# Circuit.net
KiCad netlist of a schematic drawn in EAGLE
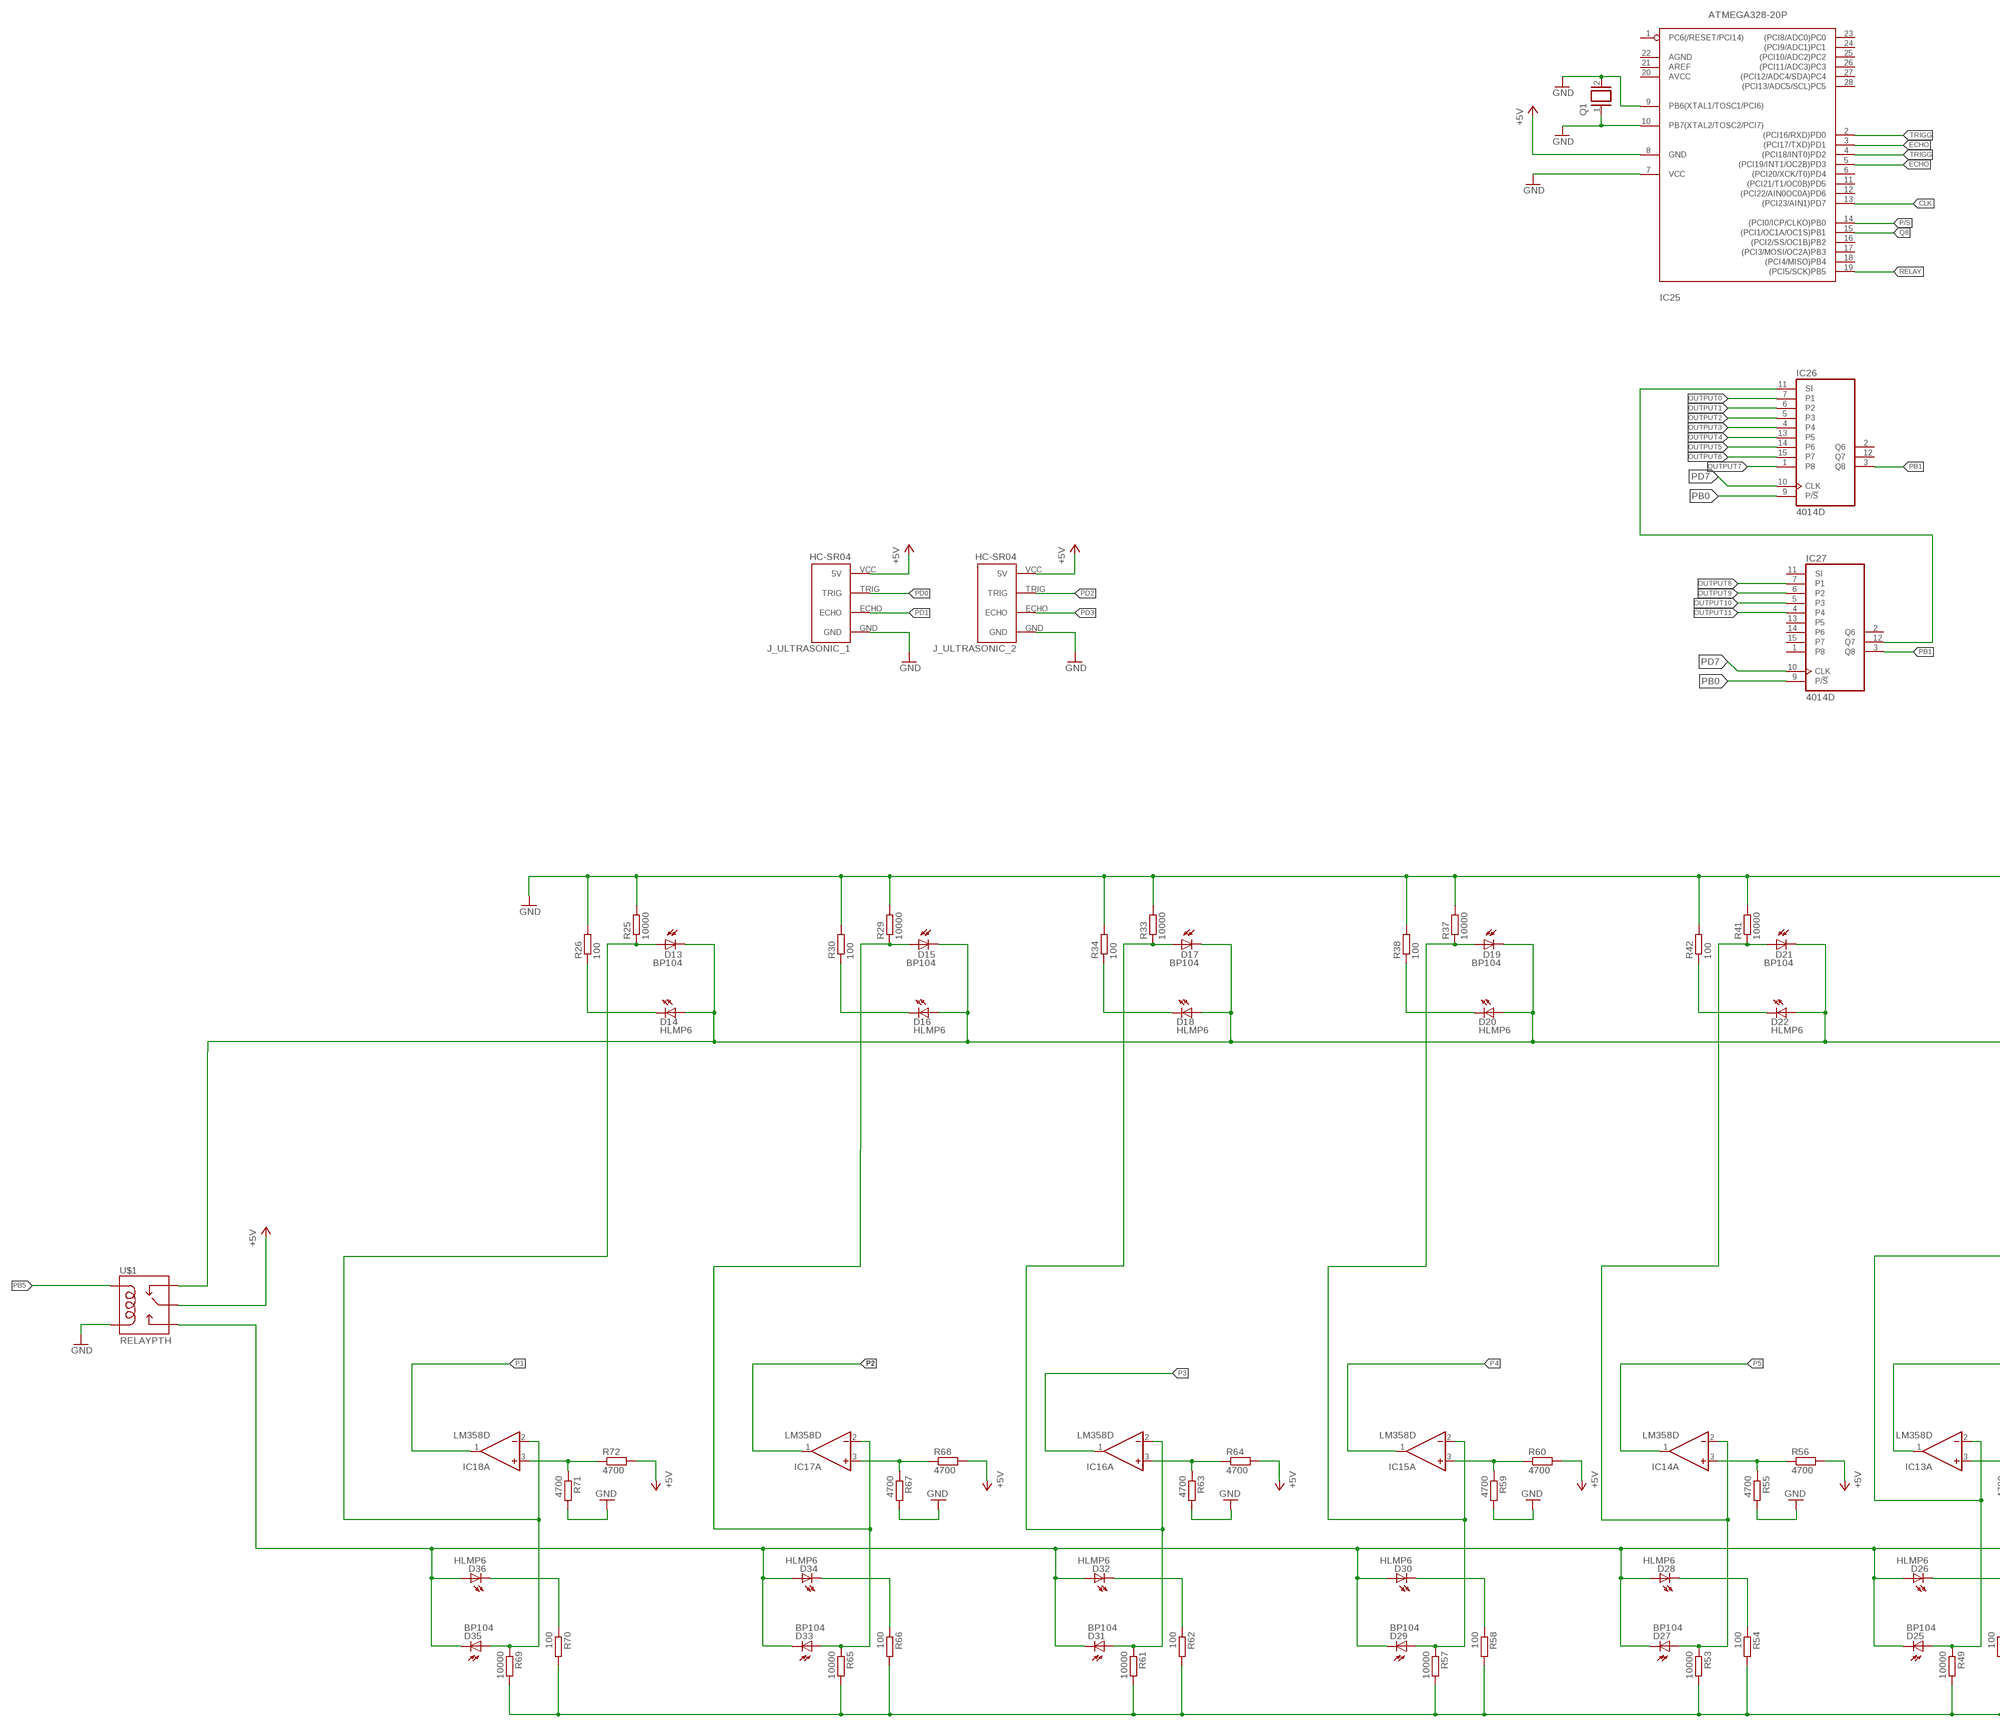
[diagram p0: schematic, sheet 1, part 1 of 2]
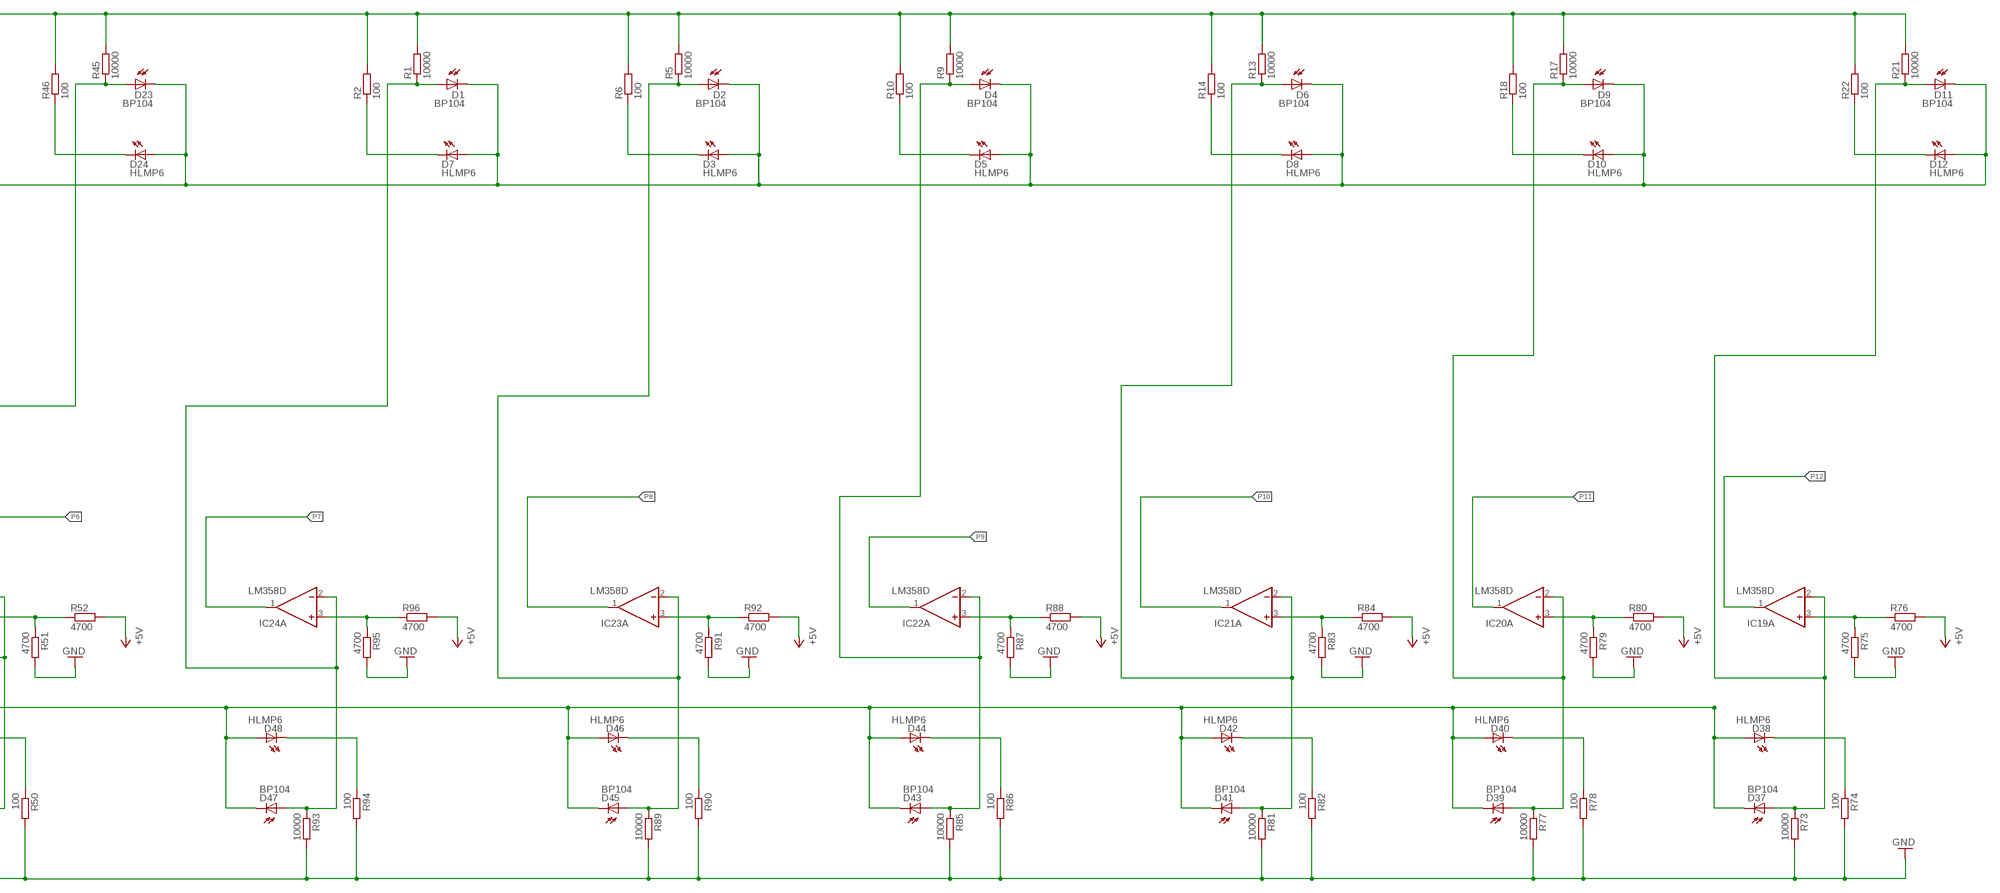
[diagram p1: schematic, sheet 1, part 2 of 2]

(export (version "E")
  (design (tool "Eeschema 10.0.6"))
  (components
    (comp (ref "D1")
      (value "BP104")
      (footprint "eagle-import:BP104")
      (fields (field (name "MF") "VISHAY/TELEFUNKEN"))
      (libsource (lib "eagle-import") (part "BP104"))
    )
    (comp (ref "D2")
      (value "BP104")
      (footprint "eagle-import:BP104")
      (fields (field (name "MF") "VISHAY/TELEFUNKEN"))
      (libsource (lib "eagle-import") (part "BP104"))
    )
    (comp (ref "D3")
      (value "HLMP6")
      (footprint "eagle-import:HLMP6")
      (fields (field (name "MF") "AGILENT TECHNOLOGIES") (field (name "MPN") "HLMP-6500"))
      (libsource (lib "eagle-import") (part "HLMP6"))
    )
    (comp (ref "D4")
      (value "BP104")
      (footprint "eagle-import:BP104")
      (fields (field (name "MF") "VISHAY/TELEFUNKEN"))
      (libsource (lib "eagle-import") (part "BP104"))
    )
    (comp (ref "D5")
      (value "HLMP6")
      (footprint "eagle-import:HLMP6")
      (fields (field (name "MF") "AGILENT TECHNOLOGIES") (field (name "MPN") "HLMP-6500"))
      (libsource (lib "eagle-import") (part "HLMP6"))
    )
    (comp (ref "D6")
      (value "BP104")
      (footprint "eagle-import:BP104")
      (fields (field (name "MF") "VISHAY/TELEFUNKEN"))
      (libsource (lib "eagle-import") (part "BP104"))
    )
    (comp (ref "D7")
      (value "HLMP6")
      (footprint "eagle-import:HLMP6")
      (fields (field (name "MF") "AGILENT TECHNOLOGIES") (field (name "MPN") "HLMP-6500"))
      (libsource (lib "eagle-import") (part "HLMP6"))
    )
    (comp (ref "D8")
      (value "HLMP6")
      (footprint "eagle-import:HLMP6")
      (fields (field (name "MF") "AGILENT TECHNOLOGIES") (field (name "MPN") "HLMP-6500"))
      (libsource (lib "eagle-import") (part "HLMP6"))
    )
    (comp (ref "D9")
      (value "BP104")
      (footprint "eagle-import:BP104")
      (fields (field (name "MF") "VISHAY/TELEFUNKEN"))
      (libsource (lib "eagle-import") (part "BP104"))
    )
    (comp (ref "D10")
      (value "HLMP6")
      (footprint "eagle-import:HLMP6")
      (fields (field (name "MF") "AGILENT TECHNOLOGIES") (field (name "MPN") "HLMP-6500"))
      (libsource (lib "eagle-import") (part "HLMP6"))
    )
    (comp (ref "D11")
      (value "BP104")
      (footprint "eagle-import:BP104")
      (fields (field (name "MF") "VISHAY/TELEFUNKEN"))
      (libsource (lib "eagle-import") (part "BP104"))
    )
    (comp (ref "D12")
      (value "HLMP6")
      (footprint "eagle-import:HLMP6")
      (fields (field (name "MF") "AGILENT TECHNOLOGIES") (field (name "MPN") "HLMP-6500"))
      (libsource (lib "eagle-import") (part "HLMP6"))
    )
    (comp (ref "D13")
      (value "BP104")
      (footprint "eagle-import:BP104")
      (fields (field (name "MF") "VISHAY/TELEFUNKEN"))
      (libsource (lib "eagle-import") (part "BP104"))
    )
    (comp (ref "D14")
      (value "HLMP6")
      (footprint "eagle-import:HLMP6")
      (fields (field (name "MF") "AGILENT TECHNOLOGIES") (field (name "MPN") "HLMP-6500"))
      (libsource (lib "eagle-import") (part "HLMP6"))
    )
    (comp (ref "D15")
      (value "BP104")
      (footprint "eagle-import:BP104")
      (fields (field (name "MF") "VISHAY/TELEFUNKEN"))
      (libsource (lib "eagle-import") (part "BP104"))
    )
    (comp (ref "D16")
      (value "HLMP6")
      (footprint "eagle-import:HLMP6")
      (fields (field (name "MF") "AGILENT TECHNOLOGIES") (field (name "MPN") "HLMP-6500"))
      (libsource (lib "eagle-import") (part "HLMP6"))
    )
    (comp (ref "D17")
      (value "BP104")
      (footprint "eagle-import:BP104")
      (fields (field (name "MF") "VISHAY/TELEFUNKEN"))
      (libsource (lib "eagle-import") (part "BP104"))
    )
    (comp (ref "D18")
      (value "HLMP6")
      (footprint "eagle-import:HLMP6")
      (fields (field (name "MF") "AGILENT TECHNOLOGIES") (field (name "MPN") "HLMP-6500"))
      (libsource (lib "eagle-import") (part "HLMP6"))
    )
    (comp (ref "D19")
      (value "BP104")
      (footprint "eagle-import:BP104")
      (fields (field (name "MF") "VISHAY/TELEFUNKEN"))
      (libsource (lib "eagle-import") (part "BP104"))
    )
    (comp (ref "D20")
      (value "HLMP6")
      (footprint "eagle-import:HLMP6")
      (fields (field (name "MF") "AGILENT TECHNOLOGIES") (field (name "MPN") "HLMP-6500"))
      (libsource (lib "eagle-import") (part "HLMP6"))
    )
    (comp (ref "D21")
      (value "BP104")
      (footprint "eagle-import:BP104")
      (fields (field (name "MF") "VISHAY/TELEFUNKEN"))
      (libsource (lib "eagle-import") (part "BP104"))
    )
    (comp (ref "D22")
      (value "HLMP6")
      (footprint "eagle-import:HLMP6")
      (fields (field (name "MF") "AGILENT TECHNOLOGIES") (field (name "MPN") "HLMP-6500"))
      (libsource (lib "eagle-import") (part "HLMP6"))
    )
    (comp (ref "D23")
      (value "BP104")
      (footprint "eagle-import:BP104")
      (fields (field (name "MF") "VISHAY/TELEFUNKEN"))
      (libsource (lib "eagle-import") (part "BP104"))
    )
    (comp (ref "D24")
      (value "HLMP6")
      (footprint "eagle-import:HLMP6")
      (fields (field (name "MF") "AGILENT TECHNOLOGIES") (field (name "MPN") "HLMP-6500"))
      (libsource (lib "eagle-import") (part "HLMP6"))
    )
    (comp (ref "D25")
      (value "BP104")
      (footprint "eagle-import:BP104")
      (fields (field (name "MF") "VISHAY/TELEFUNKEN"))
      (libsource (lib "eagle-import") (part "BP104"))
    )
    (comp (ref "D26")
      (value "HLMP6")
      (footprint "eagle-import:HLMP6")
      (fields (field (name "MF") "AGILENT TECHNOLOGIES") (field (name "MPN") "HLMP-6500"))
      (libsource (lib "eagle-import") (part "HLMP6"))
    )
    (comp (ref "D27")
      (value "BP104")
      (footprint "eagle-import:BP104")
      (fields (field (name "MF") "VISHAY/TELEFUNKEN"))
      (libsource (lib "eagle-import") (part "BP104"))
    )
    (comp (ref "D28")
      (value "HLMP6")
      (footprint "eagle-import:HLMP6")
      (fields (field (name "MF") "AGILENT TECHNOLOGIES") (field (name "MPN") "HLMP-6500"))
      (libsource (lib "eagle-import") (part "HLMP6"))
    )
    (comp (ref "D29")
      (value "BP104")
      (footprint "eagle-import:BP104")
      (fields (field (name "MF") "VISHAY/TELEFUNKEN"))
      (libsource (lib "eagle-import") (part "BP104"))
    )
    (comp (ref "D30")
      (value "HLMP6")
      (footprint "eagle-import:HLMP6")
      (fields (field (name "MF") "AGILENT TECHNOLOGIES") (field (name "MPN") "HLMP-6500"))
      (libsource (lib "eagle-import") (part "HLMP6"))
    )
    (comp (ref "D31")
      (value "BP104")
      (footprint "eagle-import:BP104")
      (fields (field (name "MF") "VISHAY/TELEFUNKEN"))
      (libsource (lib "eagle-import") (part "BP104"))
    )
    (comp (ref "D32")
      (value "HLMP6")
      (footprint "eagle-import:HLMP6")
      (fields (field (name "MF") "AGILENT TECHNOLOGIES") (field (name "MPN") "HLMP-6500"))
      (libsource (lib "eagle-import") (part "HLMP6"))
    )
    (comp (ref "D33")
      (value "BP104")
      (footprint "eagle-import:BP104")
      (fields (field (name "MF") "VISHAY/TELEFUNKEN"))
      (libsource (lib "eagle-import") (part "BP104"))
    )
    (comp (ref "D34")
      (value "HLMP6")
      (footprint "eagle-import:HLMP6")
      (fields (field (name "MF") "AGILENT TECHNOLOGIES") (field (name "MPN") "HLMP-6500"))
      (libsource (lib "eagle-import") (part "HLMP6"))
    )
    (comp (ref "D35")
      (value "BP104")
      (footprint "eagle-import:BP104")
      (fields (field (name "MF") "VISHAY/TELEFUNKEN"))
      (libsource (lib "eagle-import") (part "BP104"))
    )
    (comp (ref "D36")
      (value "HLMP6")
      (footprint "eagle-import:HLMP6")
      (fields (field (name "MF") "AGILENT TECHNOLOGIES") (field (name "MPN") "HLMP-6500"))
      (libsource (lib "eagle-import") (part "HLMP6"))
    )
    (comp (ref "D37")
      (value "BP104")
      (footprint "eagle-import:BP104")
      (fields (field (name "MF") "VISHAY/TELEFUNKEN"))
      (libsource (lib "eagle-import") (part "BP104"))
    )
    (comp (ref "D38")
      (value "HLMP6")
      (footprint "eagle-import:HLMP6")
      (fields (field (name "MF") "AGILENT TECHNOLOGIES") (field (name "MPN") "HLMP-6500"))
      (libsource (lib "eagle-import") (part "HLMP6"))
    )
    (comp (ref "D39")
      (value "BP104")
      (footprint "eagle-import:BP104")
      (fields (field (name "MF") "VISHAY/TELEFUNKEN"))
      (libsource (lib "eagle-import") (part "BP104"))
    )
    (comp (ref "D40")
      (value "HLMP6")
      (footprint "eagle-import:HLMP6")
      (fields (field (name "MF") "AGILENT TECHNOLOGIES") (field (name "MPN") "HLMP-6500"))
      (libsource (lib "eagle-import") (part "HLMP6"))
    )
    (comp (ref "D41")
      (value "BP104")
      (footprint "eagle-import:BP104")
      (fields (field (name "MF") "VISHAY/TELEFUNKEN"))
      (libsource (lib "eagle-import") (part "BP104"))
    )
    (comp (ref "D42")
      (value "HLMP6")
      (footprint "eagle-import:HLMP6")
      (fields (field (name "MF") "AGILENT TECHNOLOGIES") (field (name "MPN") "HLMP-6500"))
      (libsource (lib "eagle-import") (part "HLMP6"))
    )
    (comp (ref "D43")
      (value "BP104")
      (footprint "eagle-import:BP104")
      (fields (field (name "MF") "VISHAY/TELEFUNKEN"))
      (libsource (lib "eagle-import") (part "BP104"))
    )
    (comp (ref "D44")
      (value "HLMP6")
      (footprint "eagle-import:HLMP6")
      (fields (field (name "MF") "AGILENT TECHNOLOGIES") (field (name "MPN") "HLMP-6500"))
      (libsource (lib "eagle-import") (part "HLMP6"))
    )
    (comp (ref "D45")
      (value "BP104")
      (footprint "eagle-import:BP104")
      (fields (field (name "MF") "VISHAY/TELEFUNKEN"))
      (libsource (lib "eagle-import") (part "BP104"))
    )
    (comp (ref "D46")
      (value "HLMP6")
      (footprint "eagle-import:HLMP6")
      (fields (field (name "MF") "AGILENT TECHNOLOGIES") (field (name "MPN") "HLMP-6500"))
      (libsource (lib "eagle-import") (part "HLMP6"))
    )
    (comp (ref "D47")
      (value "BP104")
      (footprint "eagle-import:BP104")
      (fields (field (name "MF") "VISHAY/TELEFUNKEN"))
      (libsource (lib "eagle-import") (part "BP104"))
    )
    (comp (ref "D48")
      (value "HLMP6")
      (footprint "eagle-import:HLMP6")
      (fields (field (name "MF") "AGILENT TECHNOLOGIES") (field (name "MPN") "HLMP-6500"))
      (libsource (lib "eagle-import") (part "HLMP6"))
    )
    (comp (ref "IC13")
      (value "LM358D")
      (footprint "eagle-import:SO08")
      (libsource (lib "eagle-import") (part "LM358D"))
    )
    (comp (ref "IC14")
      (value "LM358D")
      (footprint "eagle-import:SO08")
      (libsource (lib "eagle-import") (part "LM358D"))
    )
    (comp (ref "IC15")
      (value "LM358D")
      (footprint "eagle-import:SO08")
      (libsource (lib "eagle-import") (part "LM358D"))
    )
    (comp (ref "IC16")
      (value "LM358D")
      (footprint "eagle-import:SO08")
      (libsource (lib "eagle-import") (part "LM358D"))
    )
    (comp (ref "IC17")
      (value "LM358D")
      (footprint "eagle-import:SO08")
      (libsource (lib "eagle-import") (part "LM358D"))
    )
    (comp (ref "IC18")
      (value "LM358D")
      (footprint "eagle-import:SO08")
      (libsource (lib "eagle-import") (part "LM358D"))
    )
    (comp (ref "IC19")
      (value "LM358D")
      (footprint "eagle-import:SO08")
      (libsource (lib "eagle-import") (part "LM358D"))
    )
    (comp (ref "IC20")
      (value "LM358D")
      (footprint "eagle-import:SO08")
      (libsource (lib "eagle-import") (part "LM358D"))
    )
    (comp (ref "IC21")
      (value "LM358D")
      (footprint "eagle-import:SO08")
      (libsource (lib "eagle-import") (part "LM358D"))
    )
    (comp (ref "IC22")
      (value "LM358D")
      (footprint "eagle-import:SO08")
      (libsource (lib "eagle-import") (part "LM358D"))
    )
    (comp (ref "IC23")
      (value "LM358D")
      (footprint "eagle-import:SO08")
      (libsource (lib "eagle-import") (part "LM358D"))
    )
    (comp (ref "IC24")
      (value "LM358D")
      (footprint "eagle-import:SO08")
      (libsource (lib "eagle-import") (part "LM358D"))
    )
    (comp (ref "IC25")
      (value "ATMEGA328-20P")
      (footprint "eagle-import:DIL28-3")
      (libsource (lib "eagle-import") (part "ATMEGA328P-20"))
    )
    (comp (ref "IC26")
      (value "4014D")
      (footprint "eagle-import:SO16")
      (libsource (lib "eagle-import") (part "4014D"))
    )
    (comp (ref "IC27")
      (value "4014D")
      (footprint "eagle-import:SO16")
      (libsource (lib "eagle-import") (part "4014D"))
    )
    (comp (ref "J_ULTRASONIC_1")
      (value "HC-SR04")
      (footprint "eagle-import:HC-SR04_FOOTPRINT")
      (libsource (lib "eagle-import") (part "HC-SR04"))
    )
    (comp (ref "J_ULTRASONIC_2")
      (value "HC-SR04")
      (footprint "eagle-import:HC-SR04_FOOTPRINT")
      (libsource (lib "eagle-import") (part "HC-SR04"))
    )
    (comp (ref "Q1")
      (value "XTAL")
      (footprint "eagle-import:Q")
      (libsource (lib "eagle-import") (part "XTAL"))
    )
    (comp (ref "R1")
      (value "10000")
      (footprint "eagle-import:0204V")
      (libsource (lib "eagle-import") (part "R-EU_0204/2V"))
    )
    (comp (ref "R2")
      (value "100")
      (footprint "eagle-import:0204V")
      (libsource (lib "eagle-import") (part "R-EU_0204/2V"))
    )
    (comp (ref "R5")
      (value "10000")
      (footprint "eagle-import:0204V")
      (libsource (lib "eagle-import") (part "R-EU_0204/2V"))
    )
    (comp (ref "R6")
      (value "100")
      (footprint "eagle-import:0204V")
      (libsource (lib "eagle-import") (part "R-EU_0204/2V"))
    )
    (comp (ref "R9")
      (value "10000")
      (footprint "eagle-import:0204V")
      (libsource (lib "eagle-import") (part "R-EU_0204/2V"))
    )
    (comp (ref "R10")
      (value "100")
      (footprint "eagle-import:0204V")
      (libsource (lib "eagle-import") (part "R-EU_0204/2V"))
    )
    (comp (ref "R13")
      (value "10000")
      (footprint "eagle-import:0204V")
      (libsource (lib "eagle-import") (part "R-EU_0204/2V"))
    )
    (comp (ref "R14")
      (value "100")
      (footprint "eagle-import:0204V")
      (libsource (lib "eagle-import") (part "R-EU_0204/2V"))
    )
    (comp (ref "R17")
      (value "10000")
      (footprint "eagle-import:0204V")
      (libsource (lib "eagle-import") (part "R-EU_0204/2V"))
    )
    (comp (ref "R18")
      (value "100")
      (footprint "eagle-import:0204V")
      (libsource (lib "eagle-import") (part "R-EU_0204/2V"))
    )
    (comp (ref "R21")
      (value "10000")
      (footprint "eagle-import:0204V")
      (libsource (lib "eagle-import") (part "R-EU_0204/2V"))
    )
    (comp (ref "R22")
      (value "100")
      (footprint "eagle-import:0204V")
      (libsource (lib "eagle-import") (part "R-EU_0204/2V"))
    )
    (comp (ref "R25")
      (value "10000")
      (footprint "eagle-import:0204V")
      (libsource (lib "eagle-import") (part "R-EU_0204/2V"))
    )
    (comp (ref "R26")
      (value "100")
      (footprint "eagle-import:0204V")
      (libsource (lib "eagle-import") (part "R-EU_0204/2V"))
    )
    (comp (ref "R29")
      (value "10000")
      (footprint "eagle-import:0204V")
      (libsource (lib "eagle-import") (part "R-EU_0204/2V"))
    )
    (comp (ref "R30")
      (value "100")
      (footprint "eagle-import:0204V")
      (libsource (lib "eagle-import") (part "R-EU_0204/2V"))
    )
    (comp (ref "R33")
      (value "10000")
      (footprint "eagle-import:0204V")
      (libsource (lib "eagle-import") (part "R-EU_0204/2V"))
    )
    (comp (ref "R34")
      (value "100")
      (footprint "eagle-import:0204V")
      (libsource (lib "eagle-import") (part "R-EU_0204/2V"))
    )
    (comp (ref "R37")
      (value "10000")
      (footprint "eagle-import:0204V")
      (libsource (lib "eagle-import") (part "R-EU_0204/2V"))
    )
    (comp (ref "R38")
      (value "100")
      (footprint "eagle-import:0204V")
      (libsource (lib "eagle-import") (part "R-EU_0204/2V"))
    )
    (comp (ref "R41")
      (value "10000")
      (footprint "eagle-import:0204V")
      (libsource (lib "eagle-import") (part "R-EU_0204/2V"))
    )
    (comp (ref "R42")
      (value "100")
      (footprint "eagle-import:0204V")
      (libsource (lib "eagle-import") (part "R-EU_0204/2V"))
    )
    (comp (ref "R45")
      (value "10000")
      (footprint "eagle-import:0204V")
      (libsource (lib "eagle-import") (part "R-EU_0204/2V"))
    )
    (comp (ref "R46")
      (value "100")
      (footprint "eagle-import:0204V")
      (libsource (lib "eagle-import") (part "R-EU_0204/2V"))
    )
    (comp (ref "R49")
      (value "10000")
      (footprint "eagle-import:0204V")
      (libsource (lib "eagle-import") (part "R-EU_0204/2V"))
    )
    (comp (ref "R50")
      (value "100")
      (footprint "eagle-import:0204V")
      (libsource (lib "eagle-import") (part "R-EU_0204/2V"))
    )
    (comp (ref "R51")
      (value "4700")
      (footprint "eagle-import:0204V")
      (libsource (lib "eagle-import") (part "R-EU_0204/2V"))
    )
    (comp (ref "R52")
      (value "4700")
      (footprint "eagle-import:0204V")
      (libsource (lib "eagle-import") (part "R-EU_0204/2V"))
    )
    (comp (ref "R53")
      (value "10000")
      (footprint "eagle-import:0204V")
      (libsource (lib "eagle-import") (part "R-EU_0204/2V"))
    )
    (comp (ref "R54")
      (value "100")
      (footprint "eagle-import:0204V")
      (libsource (lib "eagle-import") (part "R-EU_0204/2V"))
    )
    (comp (ref "R55")
      (value "4700")
      (footprint "eagle-import:0204V")
      (libsource (lib "eagle-import") (part "R-EU_0204/2V"))
    )
    (comp (ref "R56")
      (value "4700")
      (footprint "eagle-import:0204V")
      (libsource (lib "eagle-import") (part "R-EU_0204/2V"))
    )
    (comp (ref "R57")
      (value "10000")
      (footprint "eagle-import:0204V")
      (libsource (lib "eagle-import") (part "R-EU_0204/2V"))
    )
    (comp (ref "R58")
      (value "100")
      (footprint "eagle-import:0204V")
      (libsource (lib "eagle-import") (part "R-EU_0204/2V"))
    )
    (comp (ref "R59")
      (value "4700")
      (footprint "eagle-import:0204V")
      (libsource (lib "eagle-import") (part "R-EU_0204/2V"))
    )
    (comp (ref "R60")
      (value "4700")
      (footprint "eagle-import:0204V")
      (libsource (lib "eagle-import") (part "R-EU_0204/2V"))
    )
    (comp (ref "R61")
      (value "10000")
      (footprint "eagle-import:0204V")
      (libsource (lib "eagle-import") (part "R-EU_0204/2V"))
    )
    (comp (ref "R62")
      (value "100")
      (footprint "eagle-import:0204V")
      (libsource (lib "eagle-import") (part "R-EU_0204/2V"))
    )
    (comp (ref "R63")
      (value "4700")
      (footprint "eagle-import:0204V")
      (libsource (lib "eagle-import") (part "R-EU_0204/2V"))
    )
    (comp (ref "R64")
      (value "4700")
      (footprint "eagle-import:0204V")
      (libsource (lib "eagle-import") (part "R-EU_0204/2V"))
    )
    (comp (ref "R65")
      (value "10000")
      (footprint "eagle-import:0204V")
      (libsource (lib "eagle-import") (part "R-EU_0204/2V"))
    )
    (comp (ref "R66")
      (value "100")
      (footprint "eagle-import:0204V")
      (libsource (lib "eagle-import") (part "R-EU_0204/2V"))
    )
    (comp (ref "R67")
      (value "4700")
      (footprint "eagle-import:0204V")
      (libsource (lib "eagle-import") (part "R-EU_0204/2V"))
    )
    (comp (ref "R68")
      (value "4700")
      (footprint "eagle-import:0204V")
      (libsource (lib "eagle-import") (part "R-EU_0204/2V"))
    )
    (comp (ref "R69")
      (value "10000")
      (footprint "eagle-import:0204V")
      (libsource (lib "eagle-import") (part "R-EU_0204/2V"))
    )
    (comp (ref "R70")
      (value "100")
      (footprint "eagle-import:0204V")
      (libsource (lib "eagle-import") (part "R-EU_0204/2V"))
    )
    (comp (ref "R71")
      (value "4700")
      (footprint "eagle-import:0204V")
      (libsource (lib "eagle-import") (part "R-EU_0204/2V"))
    )
    (comp (ref "R72")
      (value "4700")
      (footprint "eagle-import:0204V")
      (libsource (lib "eagle-import") (part "R-EU_0204/2V"))
    )
    (comp (ref "R73")
      (value "10000")
      (footprint "eagle-import:0204V")
      (libsource (lib "eagle-import") (part "R-EU_0204/2V"))
    )
    (comp (ref "R74")
      (value "100")
      (footprint "eagle-import:0204V")
      (libsource (lib "eagle-import") (part "R-EU_0204/2V"))
    )
    (comp (ref "R75")
      (value "4700")
      (footprint "eagle-import:0204V")
      (libsource (lib "eagle-import") (part "R-EU_0204/2V"))
    )
    (comp (ref "R76")
      (value "4700")
      (footprint "eagle-import:0204V")
      (libsource (lib "eagle-import") (part "R-EU_0204/2V"))
    )
    (comp (ref "R77")
      (value "10000")
      (footprint "eagle-import:0204V")
      (libsource (lib "eagle-import") (part "R-EU_0204/2V"))
    )
    (comp (ref "R78")
      (value "100")
      (footprint "eagle-import:0204V")
      (libsource (lib "eagle-import") (part "R-EU_0204/2V"))
    )
    (comp (ref "R79")
      (value "4700")
      (footprint "eagle-import:0204V")
      (libsource (lib "eagle-import") (part "R-EU_0204/2V"))
    )
    (comp (ref "R80")
      (value "4700")
      (footprint "eagle-import:0204V")
      (libsource (lib "eagle-import") (part "R-EU_0204/2V"))
    )
    (comp (ref "R81")
      (value "10000")
      (footprint "eagle-import:0204V")
      (libsource (lib "eagle-import") (part "R-EU_0204/2V"))
    )
    (comp (ref "R82")
      (value "100")
      (footprint "eagle-import:0204V")
      (libsource (lib "eagle-import") (part "R-EU_0204/2V"))
    )
    (comp (ref "R83")
      (value "4700")
      (footprint "eagle-import:0204V")
      (libsource (lib "eagle-import") (part "R-EU_0204/2V"))
    )
    (comp (ref "R84")
      (value "4700")
      (footprint "eagle-import:0204V")
      (libsource (lib "eagle-import") (part "R-EU_0204/2V"))
    )
    (comp (ref "R85")
      (value "10000")
      (footprint "eagle-import:0204V")
      (libsource (lib "eagle-import") (part "R-EU_0204/2V"))
    )
    (comp (ref "R86")
      (value "100")
      (footprint "eagle-import:0204V")
      (libsource (lib "eagle-import") (part "R-EU_0204/2V"))
    )
    (comp (ref "R87")
      (value "4700")
      (footprint "eagle-import:0204V")
      (libsource (lib "eagle-import") (part "R-EU_0204/2V"))
    )
    (comp (ref "R88")
      (value "4700")
      (footprint "eagle-import:0204V")
      (libsource (lib "eagle-import") (part "R-EU_0204/2V"))
    )
    (comp (ref "R89")
      (value "10000")
      (footprint "eagle-import:0204V")
      (libsource (lib "eagle-import") (part "R-EU_0204/2V"))
    )
    (comp (ref "R90")
      (value "100")
      (footprint "eagle-import:0204V")
      (libsource (lib "eagle-import") (part "R-EU_0204/2V"))
    )
    (comp (ref "R91")
      (value "4700")
      (footprint "eagle-import:0204V")
      (libsource (lib "eagle-import") (part "R-EU_0204/2V"))
    )
    (comp (ref "R92")
      (value "4700")
      (footprint "eagle-import:0204V")
      (libsource (lib "eagle-import") (part "R-EU_0204/2V"))
    )
    (comp (ref "R93")
      (value "10000")
      (footprint "eagle-import:0204V")
      (libsource (lib "eagle-import") (part "R-EU_0204/2V"))
    )
    (comp (ref "R94")
      (value "100")
      (footprint "eagle-import:0204V")
      (libsource (lib "eagle-import") (part "R-EU_0204/2V"))
    )
    (comp (ref "R95")
      (value "4700")
      (footprint "eagle-import:0204V")
      (libsource (lib "eagle-import") (part "R-EU_0204/2V"))
    )
    (comp (ref "R96")
      (value "4700")
      (footprint "eagle-import:0204V")
      (libsource (lib "eagle-import") (part "R-EU_0204/2V"))
    )
    (comp (ref "U$1")
      (value "RELAYPTH")
      (footprint "eagle-import:SRD-05VDC-SL-C")
      (libsource (lib "eagle-import") (part "RELAYPTH"))
    )
  )
  (nets
    (net (code "1") (name "+5V") (class "Default")
      (node (ref "IC25") (pin "8") (pinfunction "GND_8") (pintype "bidirectional"))
      (node (ref "J_ULTRASONIC_1") (pin "VCC") (pinfunction "5V_VCC") (pintype "bidirectional"))
      (node (ref "J_ULTRASONIC_2") (pin "VCC") (pinfunction "5V_VCC") (pintype "bidirectional"))
      (node (ref "R52") (pin "2") (pinfunction "2_2") (pintype "passive"))
      (node (ref "R56") (pin "2") (pinfunction "2_2") (pintype "passive"))
      (node (ref "R60") (pin "2") (pinfunction "2_2") (pintype "passive"))
      (node (ref "R64") (pin "2") (pinfunction "2_2") (pintype "passive"))
      (node (ref "R68") (pin "2") (pinfunction "2_2") (pintype "passive"))
      (node (ref "R72") (pin "2") (pinfunction "2_2") (pintype "passive"))
      (node (ref "R76") (pin "2") (pinfunction "2_2") (pintype "passive"))
      (node (ref "R80") (pin "2") (pinfunction "2_2") (pintype "passive"))
      (node (ref "R84") (pin "2") (pinfunction "2_2") (pintype "passive"))
      (node (ref "R88") (pin "2") (pinfunction "2_2") (pintype "passive"))
      (node (ref "R92") (pin "2") (pinfunction "2_2") (pintype "passive"))
      (node (ref "R96") (pin "2") (pinfunction "2_2") (pintype "passive"))
      (node (ref "U$1") (pin "SWCOMMON") (pinfunction "SWCOMMON_SWCOMMON") (pintype "bidirectional"))
    )
    (net (code "2") (name "CLK") (class "Default")
      (node (ref "IC25") (pin "13") (pinfunction "(PCI23/AIN1)PD7_13") (pintype "bidirectional"))
    )
    (net (code "3") (name "ECHO") (class "Default")
      (node (ref "IC25") (pin "3") (pinfunction "(PCI17/TXD)PD1_3") (pintype "bidirectional"))
      (node (ref "IC25") (pin "5") (pinfunction "(PCI19/INT1/OC2B)PD3_5") (pintype "bidirectional"))
    )
    (net (code "4") (name "GND") (class "Default")
      (node (ref "IC25") (pin "10") (pinfunction "PB7(XTAL2/TOSC2/PCI7)_10") (pintype "bidirectional"))
      (node (ref "IC25") (pin "7") (pinfunction "VCC_7") (pintype "bidirectional"))
      (node (ref "IC25") (pin "9") (pinfunction "PB6(XTAL1/TOSC1/PCI6)_9") (pintype "bidirectional"))
      (node (ref "J_ULTRASONIC_1") (pin "GND") (pinfunction "GND_GND") (pintype "bidirectional"))
      (node (ref "J_ULTRASONIC_2") (pin "GND") (pinfunction "GND_GND") (pintype "bidirectional"))
      (node (ref "Q1") (pin "1") (pinfunction "1_1") (pintype "passive"))
      (node (ref "Q1") (pin "2") (pinfunction "2_2") (pintype "passive"))
      (node (ref "R1") (pin "2") (pinfunction "2_2") (pintype "passive"))
      (node (ref "R10") (pin "2") (pinfunction "2_2") (pintype "passive"))
      (node (ref "R13") (pin "2") (pinfunction "2_2") (pintype "passive"))
      (node (ref "R14") (pin "2") (pinfunction "2_2") (pintype "passive"))
      (node (ref "R17") (pin "2") (pinfunction "2_2") (pintype "passive"))
      (node (ref "R18") (pin "2") (pinfunction "2_2") (pintype "passive"))
      (node (ref "R2") (pin "2") (pinfunction "2_2") (pintype "passive"))
      (node (ref "R21") (pin "2") (pinfunction "2_2") (pintype "passive"))
      (node (ref "R22") (pin "2") (pinfunction "2_2") (pintype "passive"))
      (node (ref "R25") (pin "2") (pinfunction "2_2") (pintype "passive"))
      (node (ref "R26") (pin "2") (pinfunction "2_2") (pintype "passive"))
      (node (ref "R29") (pin "2") (pinfunction "2_2") (pintype "passive"))
      (node (ref "R30") (pin "2") (pinfunction "2_2") (pintype "passive"))
      (node (ref "R33") (pin "2") (pinfunction "2_2") (pintype "passive"))
      (node (ref "R34") (pin "2") (pinfunction "2_2") (pintype "passive"))
      (node (ref "R37") (pin "2") (pinfunction "2_2") (pintype "passive"))
      (node (ref "R38") (pin "2") (pinfunction "2_2") (pintype "passive"))
      (node (ref "R41") (pin "2") (pinfunction "2_2") (pintype "passive"))
      (node (ref "R42") (pin "2") (pinfunction "2_2") (pintype "passive"))
      (node (ref "R45") (pin "2") (pinfunction "2_2") (pintype "passive"))
      (node (ref "R46") (pin "2") (pinfunction "2_2") (pintype "passive"))
      (node (ref "R49") (pin "2") (pinfunction "2_2") (pintype "passive"))
      (node (ref "R5") (pin "2") (pinfunction "2_2") (pintype "passive"))
      (node (ref "R50") (pin "2") (pinfunction "2_2") (pintype "passive"))
      (node (ref "R51") (pin "2") (pinfunction "2_2") (pintype "passive"))
      (node (ref "R53") (pin "2") (pinfunction "2_2") (pintype "passive"))
      (node (ref "R54") (pin "2") (pinfunction "2_2") (pintype "passive"))
      (node (ref "R55") (pin "2") (pinfunction "2_2") (pintype "passive"))
      (node (ref "R57") (pin "2") (pinfunction "2_2") (pintype "passive"))
      (node (ref "R58") (pin "2") (pinfunction "2_2") (pintype "passive"))
      (node (ref "R59") (pin "2") (pinfunction "2_2") (pintype "passive"))
      (node (ref "R6") (pin "2") (pinfunction "2_2") (pintype "passive"))
      (node (ref "R61") (pin "2") (pinfunction "2_2") (pintype "passive"))
      (node (ref "R62") (pin "2") (pinfunction "2_2") (pintype "passive"))
      (node (ref "R63") (pin "2") (pinfunction "2_2") (pintype "passive"))
      (node (ref "R65") (pin "2") (pinfunction "2_2") (pintype "passive"))
      (node (ref "R66") (pin "2") (pinfunction "2_2") (pintype "passive"))
      (node (ref "R67") (pin "2") (pinfunction "2_2") (pintype "passive"))
      (node (ref "R69") (pin "2") (pinfunction "2_2") (pintype "passive"))
      (node (ref "R70") (pin "2") (pinfunction "2_2") (pintype "passive"))
      (node (ref "R71") (pin "2") (pinfunction "2_2") (pintype "passive"))
      (node (ref "R73") (pin "2") (pinfunction "2_2") (pintype "passive"))
      (node (ref "R74") (pin "2") (pinfunction "2_2") (pintype "passive"))
      (node (ref "R75") (pin "2") (pinfunction "2_2") (pintype "passive"))
      (node (ref "R77") (pin "2") (pinfunction "2_2") (pintype "passive"))
      (node (ref "R78") (pin "2") (pinfunction "2_2") (pintype "passive"))
      (node (ref "R79") (pin "2") (pinfunction "2_2") (pintype "passive"))
      (node (ref "R81") (pin "2") (pinfunction "2_2") (pintype "passive"))
      (node (ref "R82") (pin "2") (pinfunction "2_2") (pintype "passive"))
      (node (ref "R83") (pin "2") (pinfunction "2_2") (pintype "passive"))
      (node (ref "R85") (pin "2") (pinfunction "2_2") (pintype "passive"))
      (node (ref "R86") (pin "2") (pinfunction "2_2") (pintype "passive"))
      (node (ref "R87") (pin "2") (pinfunction "2_2") (pintype "passive"))
      (node (ref "R89") (pin "2") (pinfunction "2_2") (pintype "passive"))
      (node (ref "R9") (pin "2") (pinfunction "2_2") (pintype "passive"))
      (node (ref "R90") (pin "2") (pinfunction "2_2") (pintype "passive"))
      (node (ref "R91") (pin "2") (pinfunction "2_2") (pintype "passive"))
      (node (ref "R93") (pin "2") (pinfunction "2_2") (pintype "passive"))
      (node (ref "R94") (pin "2") (pinfunction "2_2") (pintype "passive"))
      (node (ref "R95") (pin "2") (pinfunction "2_2") (pintype "passive"))
      (node (ref "U$1") (pin "COIL0") (pinfunction "COIL0_COIL0") (pintype "bidirectional"))
    )
    (net (code "5") (name "Net-(D1-C)") (class "Default")
      (node (ref "D1") (pin "K") (pinfunction "C_K") (pintype "passive"))
      (node (ref "D10") (pin "A") (pinfunction "A_A") (pintype "passive"))
      (node (ref "D11") (pin "K") (pinfunction "C_K") (pintype "passive"))
      (node (ref "D12") (pin "A") (pinfunction "A_A") (pintype "passive"))
      (node (ref "D13") (pin "K") (pinfunction "C_K") (pintype "passive"))
      (node (ref "D14") (pin "A") (pinfunction "A_A") (pintype "passive"))
      (node (ref "D15") (pin "K") (pinfunction "C_K") (pintype "passive"))
      (node (ref "D16") (pin "A") (pinfunction "A_A") (pintype "passive"))
      (node (ref "D17") (pin "K") (pinfunction "C_K") (pintype "passive"))
      (node (ref "D18") (pin "A") (pinfunction "A_A") (pintype "passive"))
      (node (ref "D19") (pin "K") (pinfunction "C_K") (pintype "passive"))
      (node (ref "D2") (pin "K") (pinfunction "C_K") (pintype "passive"))
      (node (ref "D20") (pin "A") (pinfunction "A_A") (pintype "passive"))
      (node (ref "D21") (pin "K") (pinfunction "C_K") (pintype "passive"))
      (node (ref "D22") (pin "A") (pinfunction "A_A") (pintype "passive"))
      (node (ref "D23") (pin "K") (pinfunction "C_K") (pintype "passive"))
      (node (ref "D24") (pin "A") (pinfunction "A_A") (pintype "passive"))
      (node (ref "D3") (pin "A") (pinfunction "A_A") (pintype "passive"))
      (node (ref "D4") (pin "K") (pinfunction "C_K") (pintype "passive"))
      (node (ref "D5") (pin "A") (pinfunction "A_A") (pintype "passive"))
      (node (ref "D6") (pin "K") (pinfunction "C_K") (pintype "passive"))
      (node (ref "D7") (pin "A") (pinfunction "A_A") (pintype "passive"))
      (node (ref "D8") (pin "A") (pinfunction "A_A") (pintype "passive"))
      (node (ref "D9") (pin "K") (pinfunction "C_K") (pintype "passive"))
      (node (ref "U$1") (pin "SWCLOSED") (pinfunction "SWCLOSE_SWCLOSED") (pintype "bidirectional"))
    )
    (net (code "6") (name "Net-(D3-PadK)") (class "Default")
      (node (ref "D3") (pin "K") (pinfunction "K_K") (pintype "passive"))
      (node (ref "R6") (pin "1") (pinfunction "1_1") (pintype "passive"))
    )
    (net (code "7") (name "Net-(D5-PadK)") (class "Default")
      (node (ref "D5") (pin "K") (pinfunction "K_K") (pintype "passive"))
      (node (ref "R10") (pin "1") (pinfunction "1_1") (pintype "passive"))
    )
    (net (code "8") (name "Net-(D7-PadK)") (class "Default")
      (node (ref "D7") (pin "K") (pinfunction "K_K") (pintype "passive"))
      (node (ref "R2") (pin "1") (pinfunction "1_1") (pintype "passive"))
    )
    (net (code "9") (name "Net-(D8-PadK)") (class "Default")
      (node (ref "D8") (pin "K") (pinfunction "K_K") (pintype "passive"))
      (node (ref "R14") (pin "1") (pinfunction "1_1") (pintype "passive"))
    )
    (net (code "10") (name "Net-(D10-PadK)") (class "Default")
      (node (ref "D10") (pin "K") (pinfunction "K_K") (pintype "passive"))
      (node (ref "R18") (pin "1") (pinfunction "1_1") (pintype "passive"))
    )
    (net (code "11") (name "Net-(D12-PadK)") (class "Default")
      (node (ref "D12") (pin "K") (pinfunction "K_K") (pintype "passive"))
      (node (ref "R22") (pin "1") (pinfunction "1_1") (pintype "passive"))
    )
    (net (code "12") (name "Net-(D14-PadK)") (class "Default")
      (node (ref "D14") (pin "K") (pinfunction "K_K") (pintype "passive"))
      (node (ref "R26") (pin "1") (pinfunction "1_1") (pintype "passive"))
    )
    (net (code "13") (name "Net-(D16-PadK)") (class "Default")
      (node (ref "D16") (pin "K") (pinfunction "K_K") (pintype "passive"))
      (node (ref "R30") (pin "1") (pinfunction "1_1") (pintype "passive"))
    )
    (net (code "14") (name "Net-(D18-PadK)") (class "Default")
      (node (ref "D18") (pin "K") (pinfunction "K_K") (pintype "passive"))
      (node (ref "R34") (pin "1") (pinfunction "1_1") (pintype "passive"))
    )
    (net (code "15") (name "Net-(D20-PadK)") (class "Default")
      (node (ref "D20") (pin "K") (pinfunction "K_K") (pintype "passive"))
      (node (ref "R38") (pin "1") (pinfunction "1_1") (pintype "passive"))
    )
    (net (code "16") (name "Net-(D22-PadK)") (class "Default")
      (node (ref "D22") (pin "K") (pinfunction "K_K") (pintype "passive"))
      (node (ref "R42") (pin "1") (pinfunction "1_1") (pintype "passive"))
    )
    (net (code "17") (name "Net-(D24-PadK)") (class "Default")
      (node (ref "D24") (pin "K") (pinfunction "K_K") (pintype "passive"))
      (node (ref "R46") (pin "1") (pinfunction "1_1") (pintype "passive"))
    )
    (net (code "18") (name "Net-(D25-C)") (class "Default")
      (node (ref "D25") (pin "K") (pinfunction "C_K") (pintype "passive"))
      (node (ref "D26") (pin "A") (pinfunction "A_A") (pintype "passive"))
      (node (ref "D27") (pin "K") (pinfunction "C_K") (pintype "passive"))
      (node (ref "D28") (pin "A") (pinfunction "A_A") (pintype "passive"))
      (node (ref "D29") (pin "K") (pinfunction "C_K") (pintype "passive"))
      (node (ref "D30") (pin "A") (pinfunction "A_A") (pintype "passive"))
      (node (ref "D31") (pin "K") (pinfunction "C_K") (pintype "passive"))
      (node (ref "D32") (pin "A") (pinfunction "A_A") (pintype "passive"))
      (node (ref "D33") (pin "K") (pinfunction "C_K") (pintype "passive"))
      (node (ref "D34") (pin "A") (pinfunction "A_A") (pintype "passive"))
      (node (ref "D35") (pin "K") (pinfunction "C_K") (pintype "passive"))
      (node (ref "D36") (pin "A") (pinfunction "A_A") (pintype "passive"))
      (node (ref "D37") (pin "K") (pinfunction "C_K") (pintype "passive"))
      (node (ref "D38") (pin "A") (pinfunction "A_A") (pintype "passive"))
      (node (ref "D39") (pin "K") (pinfunction "C_K") (pintype "passive"))
      (node (ref "D40") (pin "A") (pinfunction "A_A") (pintype "passive"))
      (node (ref "D41") (pin "K") (pinfunction "C_K") (pintype "passive"))
      (node (ref "D42") (pin "A") (pinfunction "A_A") (pintype "passive"))
      (node (ref "D43") (pin "K") (pinfunction "C_K") (pintype "passive"))
      (node (ref "D44") (pin "A") (pinfunction "A_A") (pintype "passive"))
      (node (ref "D45") (pin "K") (pinfunction "C_K") (pintype "passive"))
      (node (ref "D46") (pin "A") (pinfunction "A_A") (pintype "passive"))
      (node (ref "D47") (pin "K") (pinfunction "C_K") (pintype "passive"))
      (node (ref "D48") (pin "A") (pinfunction "A_A") (pintype "passive"))
      (node (ref "U$1") (pin "SWOPEN") (pinfunction "SWOPEN_SWOPEN") (pintype "bidirectional"))
    )
    (net (code "19") (name "Net-(D26-PadK)") (class "Default")
      (node (ref "D26") (pin "K") (pinfunction "K_K") (pintype "passive"))
      (node (ref "R50") (pin "1") (pinfunction "1_1") (pintype "passive"))
    )
    (net (code "20") (name "Net-(D28-PadK)") (class "Default")
      (node (ref "D28") (pin "K") (pinfunction "K_K") (pintype "passive"))
      (node (ref "R54") (pin "1") (pinfunction "1_1") (pintype "passive"))
    )
    (net (code "21") (name "Net-(D30-PadK)") (class "Default")
      (node (ref "D30") (pin "K") (pinfunction "K_K") (pintype "passive"))
      (node (ref "R58") (pin "1") (pinfunction "1_1") (pintype "passive"))
    )
    (net (code "22") (name "Net-(D32-PadK)") (class "Default")
      (node (ref "D32") (pin "K") (pinfunction "K_K") (pintype "passive"))
      (node (ref "R62") (pin "1") (pinfunction "1_1") (pintype "passive"))
    )
    (net (code "23") (name "Net-(D34-PadK)") (class "Default")
      (node (ref "D34") (pin "K") (pinfunction "K_K") (pintype "passive"))
      (node (ref "R66") (pin "1") (pinfunction "1_1") (pintype "passive"))
    )
    (net (code "24") (name "Net-(D36-PadK)") (class "Default")
      (node (ref "D36") (pin "K") (pinfunction "K_K") (pintype "passive"))
      (node (ref "R70") (pin "1") (pinfunction "1_1") (pintype "passive"))
    )
    (net (code "25") (name "Net-(D38-PadK)") (class "Default")
      (node (ref "D38") (pin "K") (pinfunction "K_K") (pintype "passive"))
      (node (ref "R74") (pin "1") (pinfunction "1_1") (pintype "passive"))
    )
    (net (code "26") (name "Net-(D40-PadK)") (class "Default")
      (node (ref "D40") (pin "K") (pinfunction "K_K") (pintype "passive"))
      (node (ref "R78") (pin "1") (pinfunction "1_1") (pintype "passive"))
    )
    (net (code "27") (name "Net-(D42-PadK)") (class "Default")
      (node (ref "D42") (pin "K") (pinfunction "K_K") (pintype "passive"))
      (node (ref "R82") (pin "1") (pinfunction "1_1") (pintype "passive"))
    )
    (net (code "28") (name "Net-(D44-PadK)") (class "Default")
      (node (ref "D44") (pin "K") (pinfunction "K_K") (pintype "passive"))
      (node (ref "R86") (pin "1") (pinfunction "1_1") (pintype "passive"))
    )
    (net (code "29") (name "Net-(D46-PadK)") (class "Default")
      (node (ref "D46") (pin "K") (pinfunction "K_K") (pintype "passive"))
      (node (ref "R90") (pin "1") (pinfunction "1_1") (pintype "passive"))
    )
    (net (code "30") (name "Net-(D48-PadK)") (class "Default")
      (node (ref "D48") (pin "K") (pinfunction "K_K") (pintype "passive"))
      (node (ref "R94") (pin "1") (pinfunction "1_1") (pintype "passive"))
    )
    (net (code "31") (name "Net-(IC13A-+IN)") (class "Default")
      (node (ref "IC13") (pin "3") (pinfunction "+IN_3") (pintype "input"))
      (node (ref "R51") (pin "1") (pinfunction "1_1") (pintype "passive"))
      (node (ref "R52") (pin "1") (pinfunction "1_1") (pintype "passive"))
    )
    (net (code "32") (name "Net-(IC13A--IN)") (class "Default")
      (node (ref "D23") (pin "A") (pinfunction "A_A") (pintype "passive"))
      (node (ref "D25") (pin "A") (pinfunction "A_A") (pintype "passive"))
      (node (ref "IC13") (pin "2") (pinfunction "-IN_2") (pintype "input"))
      (node (ref "R45") (pin "1") (pinfunction "1_1") (pintype "passive"))
      (node (ref "R49") (pin "1") (pinfunction "1_1") (pintype "passive"))
    )
    (net (code "33") (name "Net-(IC14A-+IN)") (class "Default")
      (node (ref "IC14") (pin "3") (pinfunction "+IN_3") (pintype "input"))
      (node (ref "R55") (pin "1") (pinfunction "1_1") (pintype "passive"))
      (node (ref "R56") (pin "1") (pinfunction "1_1") (pintype "passive"))
    )
    (net (code "34") (name "Net-(IC14A--IN)") (class "Default")
      (node (ref "D21") (pin "A") (pinfunction "A_A") (pintype "passive"))
      (node (ref "D27") (pin "A") (pinfunction "A_A") (pintype "passive"))
      (node (ref "IC14") (pin "2") (pinfunction "-IN_2") (pintype "input"))
      (node (ref "R41") (pin "1") (pinfunction "1_1") (pintype "passive"))
      (node (ref "R53") (pin "1") (pinfunction "1_1") (pintype "passive"))
    )
    (net (code "35") (name "Net-(IC15A-+IN)") (class "Default")
      (node (ref "IC15") (pin "3") (pinfunction "+IN_3") (pintype "input"))
      (node (ref "R59") (pin "1") (pinfunction "1_1") (pintype "passive"))
      (node (ref "R60") (pin "1") (pinfunction "1_1") (pintype "passive"))
    )
    (net (code "36") (name "Net-(IC15A--IN)") (class "Default")
      (node (ref "D19") (pin "A") (pinfunction "A_A") (pintype "passive"))
      (node (ref "D29") (pin "A") (pinfunction "A_A") (pintype "passive"))
      (node (ref "IC15") (pin "2") (pinfunction "-IN_2") (pintype "input"))
      (node (ref "R37") (pin "1") (pinfunction "1_1") (pintype "passive"))
      (node (ref "R57") (pin "1") (pinfunction "1_1") (pintype "passive"))
    )
    (net (code "37") (name "Net-(IC16A-+IN)") (class "Default")
      (node (ref "IC16") (pin "3") (pinfunction "+IN_3") (pintype "input"))
      (node (ref "R63") (pin "1") (pinfunction "1_1") (pintype "passive"))
      (node (ref "R64") (pin "1") (pinfunction "1_1") (pintype "passive"))
    )
    (net (code "38") (name "Net-(IC16A--IN)") (class "Default")
      (node (ref "D17") (pin "A") (pinfunction "A_A") (pintype "passive"))
      (node (ref "D31") (pin "A") (pinfunction "A_A") (pintype "passive"))
      (node (ref "IC16") (pin "2") (pinfunction "-IN_2") (pintype "input"))
      (node (ref "R33") (pin "1") (pinfunction "1_1") (pintype "passive"))
      (node (ref "R61") (pin "1") (pinfunction "1_1") (pintype "passive"))
    )
    (net (code "39") (name "Net-(IC17A-+IN)") (class "Default")
      (node (ref "IC17") (pin "3") (pinfunction "+IN_3") (pintype "input"))
      (node (ref "R67") (pin "1") (pinfunction "1_1") (pintype "passive"))
      (node (ref "R68") (pin "1") (pinfunction "1_1") (pintype "passive"))
    )
    (net (code "40") (name "Net-(IC17A--IN)") (class "Default")
      (node (ref "D15") (pin "A") (pinfunction "A_A") (pintype "passive"))
      (node (ref "D33") (pin "A") (pinfunction "A_A") (pintype "passive"))
      (node (ref "IC17") (pin "2") (pinfunction "-IN_2") (pintype "input"))
      (node (ref "R29") (pin "1") (pinfunction "1_1") (pintype "passive"))
      (node (ref "R65") (pin "1") (pinfunction "1_1") (pintype "passive"))
    )
    (net (code "41") (name "Net-(IC18A-+IN)") (class "Default")
      (node (ref "IC18") (pin "3") (pinfunction "+IN_3") (pintype "input"))
      (node (ref "R71") (pin "1") (pinfunction "1_1") (pintype "passive"))
      (node (ref "R72") (pin "1") (pinfunction "1_1") (pintype "passive"))
    )
    (net (code "42") (name "Net-(IC18A--IN)") (class "Default")
      (node (ref "D13") (pin "A") (pinfunction "A_A") (pintype "passive"))
      (node (ref "D35") (pin "A") (pinfunction "A_A") (pintype "passive"))
      (node (ref "IC18") (pin "2") (pinfunction "-IN_2") (pintype "input"))
      (node (ref "R25") (pin "1") (pinfunction "1_1") (pintype "passive"))
      (node (ref "R69") (pin "1") (pinfunction "1_1") (pintype "passive"))
    )
    (net (code "43") (name "Net-(IC19A-+IN)") (class "Default")
      (node (ref "IC19") (pin "3") (pinfunction "+IN_3") (pintype "input"))
      (node (ref "R75") (pin "1") (pinfunction "1_1") (pintype "passive"))
      (node (ref "R76") (pin "1") (pinfunction "1_1") (pintype "passive"))
    )
    (net (code "44") (name "Net-(IC19A--IN)") (class "Default")
      (node (ref "D11") (pin "A") (pinfunction "A_A") (pintype "passive"))
      (node (ref "D37") (pin "A") (pinfunction "A_A") (pintype "passive"))
      (node (ref "IC19") (pin "2") (pinfunction "-IN_2") (pintype "input"))
      (node (ref "R21") (pin "1") (pinfunction "1_1") (pintype "passive"))
      (node (ref "R73") (pin "1") (pinfunction "1_1") (pintype "passive"))
    )
    (net (code "45") (name "Net-(IC20A-+IN)") (class "Default")
      (node (ref "IC20") (pin "3") (pinfunction "+IN_3") (pintype "input"))
      (node (ref "R79") (pin "1") (pinfunction "1_1") (pintype "passive"))
      (node (ref "R80") (pin "1") (pinfunction "1_1") (pintype "passive"))
    )
    (net (code "46") (name "Net-(IC20A--IN)") (class "Default")
      (node (ref "D39") (pin "A") (pinfunction "A_A") (pintype "passive"))
      (node (ref "D9") (pin "A") (pinfunction "A_A") (pintype "passive"))
      (node (ref "IC20") (pin "2") (pinfunction "-IN_2") (pintype "input"))
      (node (ref "R17") (pin "1") (pinfunction "1_1") (pintype "passive"))
      (node (ref "R77") (pin "1") (pinfunction "1_1") (pintype "passive"))
    )
    (net (code "47") (name "Net-(IC21A-+IN)") (class "Default")
      (node (ref "IC21") (pin "3") (pinfunction "+IN_3") (pintype "input"))
      (node (ref "R83") (pin "1") (pinfunction "1_1") (pintype "passive"))
      (node (ref "R84") (pin "1") (pinfunction "1_1") (pintype "passive"))
    )
    (net (code "48") (name "Net-(IC21A--IN)") (class "Default")
      (node (ref "D41") (pin "A") (pinfunction "A_A") (pintype "passive"))
      (node (ref "D6") (pin "A") (pinfunction "A_A") (pintype "passive"))
      (node (ref "IC21") (pin "2") (pinfunction "-IN_2") (pintype "input"))
      (node (ref "R13") (pin "1") (pinfunction "1_1") (pintype "passive"))
      (node (ref "R81") (pin "1") (pinfunction "1_1") (pintype "passive"))
    )
    (net (code "49") (name "Net-(IC22A-+IN)") (class "Default")
      (node (ref "IC22") (pin "3") (pinfunction "+IN_3") (pintype "input"))
      (node (ref "R87") (pin "1") (pinfunction "1_1") (pintype "passive"))
      (node (ref "R88") (pin "1") (pinfunction "1_1") (pintype "passive"))
    )
    (net (code "50") (name "Net-(IC22A--IN)") (class "Default")
      (node (ref "D4") (pin "A") (pinfunction "A_A") (pintype "passive"))
      (node (ref "D43") (pin "A") (pinfunction "A_A") (pintype "passive"))
      (node (ref "IC22") (pin "2") (pinfunction "-IN_2") (pintype "input"))
      (node (ref "R85") (pin "1") (pinfunction "1_1") (pintype "passive"))
      (node (ref "R9") (pin "1") (pinfunction "1_1") (pintype "passive"))
    )
    (net (code "51") (name "Net-(IC23A-+IN)") (class "Default")
      (node (ref "IC23") (pin "3") (pinfunction "+IN_3") (pintype "input"))
      (node (ref "R91") (pin "1") (pinfunction "1_1") (pintype "passive"))
      (node (ref "R92") (pin "1") (pinfunction "1_1") (pintype "passive"))
    )
    (net (code "52") (name "Net-(IC23A--IN)") (class "Default")
      (node (ref "D2") (pin "A") (pinfunction "A_A") (pintype "passive"))
      (node (ref "D45") (pin "A") (pinfunction "A_A") (pintype "passive"))
      (node (ref "IC23") (pin "2") (pinfunction "-IN_2") (pintype "input"))
      (node (ref "R5") (pin "1") (pinfunction "1_1") (pintype "passive"))
      (node (ref "R89") (pin "1") (pinfunction "1_1") (pintype "passive"))
    )
    (net (code "53") (name "Net-(IC24A-+IN)") (class "Default")
      (node (ref "IC24") (pin "3") (pinfunction "+IN_3") (pintype "input"))
      (node (ref "R95") (pin "1") (pinfunction "1_1") (pintype "passive"))
      (node (ref "R96") (pin "1") (pinfunction "1_1") (pintype "passive"))
    )
    (net (code "54") (name "Net-(IC24A--IN)") (class "Default")
      (node (ref "D1") (pin "A") (pinfunction "A_A") (pintype "passive"))
      (node (ref "D47") (pin "A") (pinfunction "A_A") (pintype "passive"))
      (node (ref "IC24") (pin "2") (pinfunction "-IN_2") (pintype "input"))
      (node (ref "R1") (pin "1") (pinfunction "1_1") (pintype "passive"))
      (node (ref "R93") (pin "1") (pinfunction "1_1") (pintype "passive"))
    )
    (net (code "55") (name "Net-(IC26A-SI)") (class "Default")
      (node (ref "IC26") (pin "11") (pinfunction "SI_11") (pintype "input"))
      (node (ref "IC27") (pin "12") (pinfunction "Q7_12") (pintype "output"))
    )
    (net (code "56") (name "OUTPUT0") (class "Default")
      (node (ref "IC26") (pin "7") (pinfunction "P1_7") (pintype "input"))
    )
    (net (code "57") (name "OUTPUT1") (class "Default")
      (node (ref "IC26") (pin "6") (pinfunction "P2_6") (pintype "input"))
    )
    (net (code "58") (name "OUTPUT2") (class "Default")
      (node (ref "IC26") (pin "5") (pinfunction "P3_5") (pintype "input"))
    )
    (net (code "59") (name "OUTPUT3") (class "Default")
      (node (ref "IC26") (pin "4") (pinfunction "P4_4") (pintype "input"))
    )
    (net (code "60") (name "OUTPUT4") (class "Default")
      (node (ref "IC26") (pin "13") (pinfunction "P5_13") (pintype "input"))
    )
    (net (code "61") (name "OUTPUT5") (class "Default")
      (node (ref "IC26") (pin "14") (pinfunction "P6_14") (pintype "input"))
    )
    (net (code "62") (name "OUTPUT6") (class "Default")
      (node (ref "IC26") (pin "15") (pinfunction "P7_15") (pintype "input"))
    )
    (net (code "63") (name "OUTPUT7") (class "Default")
      (node (ref "IC26") (pin "1") (pinfunction "P8_1") (pintype "input"))
    )
    (net (code "64") (name "OUTPUT8") (class "Default")
      (node (ref "IC27") (pin "7") (pinfunction "P1_7") (pintype "input"))
    )
    (net (code "65") (name "OUTPUT9") (class "Default")
      (node (ref "IC27") (pin "6") (pinfunction "P2_6") (pintype "input"))
    )
    (net (code "66") (name "OUTPUT10") (class "Default")
      (node (ref "IC27") (pin "5") (pinfunction "P3_5") (pintype "input"))
    )
    (net (code "67") (name "OUTPUT11") (class "Default")
      (node (ref "IC27") (pin "4") (pinfunction "P4_4") (pintype "input"))
    )
    (net (code "68") (name "P1") (class "Default")
      (node (ref "IC18") (pin "1") (pinfunction "OUT_1") (pintype "output"))
    )
    (net (code "69") (name "P2") (class "Default")
      (node (ref "IC17") (pin "1") (pinfunction "OUT_1") (pintype "output"))
    )
    (net (code "70") (name "P3") (class "Default")
      (node (ref "IC16") (pin "1") (pinfunction "OUT_1") (pintype "output"))
    )
    (net (code "71") (name "P4") (class "Default")
      (node (ref "IC15") (pin "1") (pinfunction "OUT_1") (pintype "output"))
    )
    (net (code "72") (name "P5") (class "Default")
      (node (ref "IC14") (pin "1") (pinfunction "OUT_1") (pintype "output"))
    )
    (net (code "73") (name "P6") (class "Default")
      (node (ref "IC13") (pin "1") (pinfunction "OUT_1") (pintype "output"))
    )
    (net (code "74") (name "P7") (class "Default")
      (node (ref "IC24") (pin "1") (pinfunction "OUT_1") (pintype "output"))
    )
    (net (code "75") (name "P8") (class "Default")
      (node (ref "IC23") (pin "1") (pinfunction "OUT_1") (pintype "output"))
    )
    (net (code "76") (name "P9") (class "Default")
      (node (ref "IC22") (pin "1") (pinfunction "OUT_1") (pintype "output"))
    )
    (net (code "77") (name "P10") (class "Default")
      (node (ref "IC21") (pin "1") (pinfunction "OUT_1") (pintype "output"))
    )
    (net (code "78") (name "P11") (class "Default")
      (node (ref "IC20") (pin "1") (pinfunction "OUT_1") (pintype "output"))
    )
    (net (code "79") (name "P12") (class "Default")
      (node (ref "IC19") (pin "1") (pinfunction "OUT_1") (pintype "output"))
    )
    (net (code "80") (name "PB0") (class "Default")
      (node (ref "IC26") (pin "10") (pinfunction "CLK_10") (pintype "input"))
      (node (ref "IC27") (pin "10") (pinfunction "CLK_10") (pintype "input"))
    )
    (net (code "81") (name "PB1") (class "Default")
      (node (ref "IC26") (pin "3") (pinfunction "Q8_3") (pintype "output"))
      (node (ref "IC27") (pin "3") (pinfunction "Q8_3") (pintype "output"))
    )
    (net (code "82") (name "PB5") (class "Default")
      (node (ref "U$1") (pin "COIL1") (pinfunction "COIL1_COIL1") (pintype "bidirectional"))
    )
    (net (code "83") (name "PD0") (class "Default")
      (node (ref "J_ULTRASONIC_1") (pin "TRIG") (pinfunction "TRIG_TRIG") (pintype "bidirectional"))
    )
    (net (code "84") (name "PD1") (class "Default")
      (node (ref "J_ULTRASONIC_1") (pin "ECHO") (pinfunction "ECHO_ECHO") (pintype "bidirectional"))
    )
    (net (code "85") (name "PD2") (class "Default")
      (node (ref "J_ULTRASONIC_2") (pin "TRIG") (pinfunction "TRIG_TRIG") (pintype "bidirectional"))
    )
    (net (code "86") (name "PD3") (class "Default")
      (node (ref "J_ULTRASONIC_2") (pin "ECHO") (pinfunction "ECHO_ECHO") (pintype "bidirectional"))
    )
    (net (code "87") (name "P{slash}S") (class "Default")
      (node (ref "IC25") (pin "14") (pinfunction "(PCI0/ICP/CLKO)PB0_14") (pintype "bidirectional"))
    )
    (net (code "88") (name "Q8") (class "Default")
      (node (ref "IC25") (pin "15") (pinfunction "(PCI1/OC1A/OC1S)PB1_15") (pintype "bidirectional"))
    )
    (net (code "89") (name "RELAY") (class "Default")
      (node (ref "IC25") (pin "19") (pinfunction "(PCI5/SCK)PB5_19") (pintype "bidirectional"))
    )
    (net (code "90") (name "TRIGG") (class "Default")
      (node (ref "IC25") (pin "2") (pinfunction "(PCI16/RXD)PD0_2") (pintype "bidirectional"))
      (node (ref "IC25") (pin "4") (pinfunction "(PCI18/INT0)PD2_4") (pintype "bidirectional"))
    )
    (net (code "91") (name "unconnected-(IC25-(PCI2{slash}SS{slash}OC1B)PB2-Pad16)") (class "Default")
      (node (ref "IC25") (pin "16") (pinfunction "(PCI2/SS/OC1B)PB2_16") (pintype "bidirectional"))
    )
    (net (code "92") (name "unconnected-(IC25-(PCI3{slash}MOSI{slash}OC2A)PB3-Pad17)") (class "Default")
      (node (ref "IC25") (pin "17") (pinfunction "(PCI3/MOSI/OC2A)PB3_17") (pintype "bidirectional"))
    )
    (net (code "93") (name "unconnected-(IC25-(PCI4{slash}MISO)PB4-Pad18)") (class "Default")
      (node (ref "IC25") (pin "18") (pinfunction "(PCI4/MISO)PB4_18") (pintype "bidirectional"))
    )
    (net (code "94") (name "unconnected-(IC25-(PCI8{slash}ADC0)PC0-Pad23)") (class "Default")
      (node (ref "IC25") (pin "23") (pinfunction "(PCI8/ADC0)PC0_23") (pintype "bidirectional"))
    )
    (net (code "95") (name "unconnected-(IC25-(PCI9{slash}ADC1)PC1-Pad24)") (class "Default")
      (node (ref "IC25") (pin "24") (pinfunction "(PCI9/ADC1)PC1_24") (pintype "bidirectional"))
    )
    (net (code "96") (name "unconnected-(IC25-(PCI10{slash}ADC2)PC2-Pad25)") (class "Default")
      (node (ref "IC25") (pin "25") (pinfunction "(PCI10/ADC2)PC2_25") (pintype "bidirectional"))
    )
    (net (code "97") (name "unconnected-(IC25-(PCI11{slash}ADC3)PC3-Pad26)") (class "Default")
      (node (ref "IC25") (pin "26") (pinfunction "(PCI11/ADC3)PC3_26") (pintype "bidirectional"))
    )
    (net (code "98") (name "unconnected-(IC25-(PCI12{slash}ADC4{slash}SDA)PC4-Pad27)") (class "Default")
      (node (ref "IC25") (pin "27") (pinfunction "(PCI12/ADC4/SDA)PC4_27") (pintype "bidirectional"))
    )
    (net (code "99") (name "unconnected-(IC25-(PCI13{slash}ADC5{slash}SCL)PC5-Pad28)") (class "Default")
      (node (ref "IC25") (pin "28") (pinfunction "(PCI13/ADC5/SCL)PC5_28") (pintype "bidirectional"))
    )
    (net (code "100") (name "unconnected-(IC25-(PCI20{slash}XCK{slash}T0)PD4-Pad6)") (class "Default")
      (node (ref "IC25") (pin "6") (pinfunction "(PCI20/XCK/T0)PD4_6") (pintype "bidirectional"))
    )
    (net (code "101") (name "unconnected-(IC25-(PCI21{slash}T1{slash}OC0B)PD5-Pad11)") (class "Default")
      (node (ref "IC25") (pin "11") (pinfunction "(PCI21/T1/OC0B)PD5_11") (pintype "bidirectional"))
    )
    (net (code "102") (name "unconnected-(IC25-(PCI22{slash}AIN0OC0A)PD6-Pad12)") (class "Default")
      (node (ref "IC25") (pin "12") (pinfunction "(PCI22/AIN0OC0A)PD6_12") (pintype "bidirectional"))
    )
    (net (code "103") (name "unconnected-(IC25-AGND-Pad22)") (class "Default")
      (node (ref "IC25") (pin "22") (pinfunction "AGND_22") (pintype "bidirectional"))
    )
    (net (code "104") (name "unconnected-(IC25-AREF-Pad21)") (class "Default")
      (node (ref "IC25") (pin "21") (pinfunction "AREF_21") (pintype "bidirectional"))
    )
    (net (code "105") (name "unconnected-(IC25-AVCC-Pad20)") (class "Default")
      (node (ref "IC25") (pin "20") (pinfunction "AVCC_20") (pintype "bidirectional"))
    )
    (net (code "106") (name "unconnected-(IC25-PC6({slash}RESET{slash}PCI14)-Pad1)") (class "Default")
      (node (ref "IC25") (pin "1") (pinfunction "PC6(/RESET/PCI14)_1") (pintype "bidirectional"))
    )
    (net (code "107") (name "unconnected-(IC26A-P{slash}~{S}-Pad9)") (class "Default")
      (node (ref "IC26") (pin "9") (pinfunction "P/~{S}_9") (pintype "input"))
    )
    (net (code "108") (name "unconnected-(IC26A-Q6-Pad2)") (class "Default")
      (node (ref "IC26") (pin "2") (pinfunction "Q6_2") (pintype "output"))
    )
    (net (code "109") (name "unconnected-(IC26A-Q7-Pad12)") (class "Default")
      (node (ref "IC26") (pin "12") (pinfunction "Q7_12") (pintype "output"))
    )
    (net (code "110") (name "unconnected-(IC27A-P5-Pad13)") (class "Default")
      (node (ref "IC27") (pin "13") (pinfunction "P5_13") (pintype "input"))
    )
    (net (code "111") (name "unconnected-(IC27A-P6-Pad14)") (class "Default")
      (node (ref "IC27") (pin "14") (pinfunction "P6_14") (pintype "input"))
    )
    (net (code "112") (name "unconnected-(IC27A-P7-Pad15)") (class "Default")
      (node (ref "IC27") (pin "15") (pinfunction "P7_15") (pintype "input"))
    )
    (net (code "113") (name "unconnected-(IC27A-P8-Pad1)") (class "Default")
      (node (ref "IC27") (pin "1") (pinfunction "P8_1") (pintype "input"))
    )
    (net (code "114") (name "unconnected-(IC27A-P{slash}~{S}-Pad9)") (class "Default")
      (node (ref "IC27") (pin "9") (pinfunction "P/~{S}_9") (pintype "input"))
    )
    (net (code "115") (name "unconnected-(IC27A-Q6-Pad2)") (class "Default")
      (node (ref "IC27") (pin "2") (pinfunction "Q6_2") (pintype "output"))
    )
    (net (code "116") (name "unconnected-(IC27A-SI-Pad11)") (class "Default")
      (node (ref "IC27") (pin "11") (pinfunction "SI_11") (pintype "input"))
    )
  )
)
